# gyro_acc.net
KiCad netlist of a schematic drawn in EAGLE
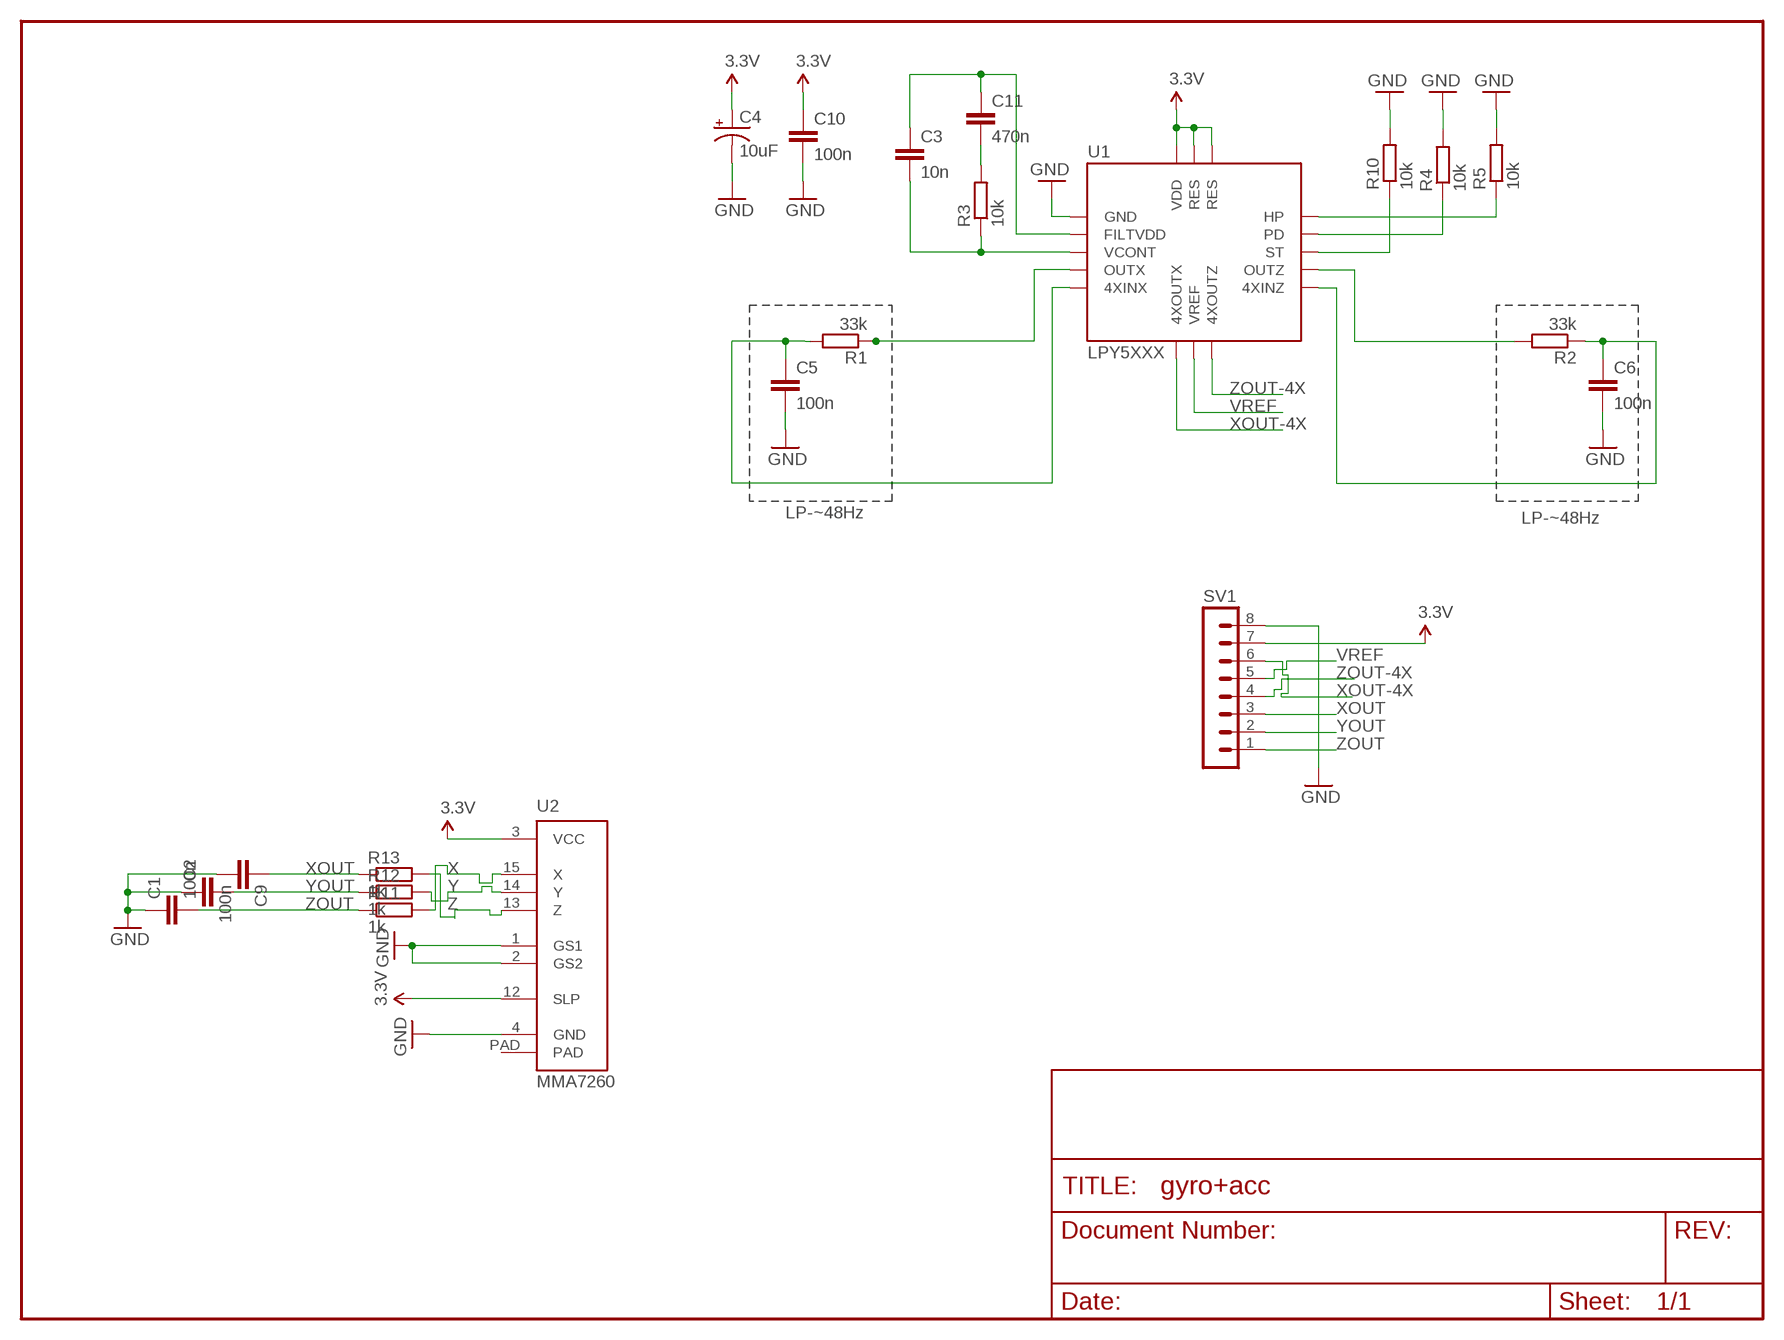
[diagram p0: schematic, sheet 1]

(export (version "E")
  (design (tool "Eeschema 10.0.6"))
  (components
    (comp (ref "C1")
      (value "100n")
      (footprint "eagle-import:C1206")
      (libsource (lib "eagle-import") (part "C-EUC1206"))
    )
    (comp (ref "C2")
      (value "C-EUC1206")
      (footprint "eagle-import:C1206")
      (libsource (lib "eagle-import") (part "C-EUC1206"))
    )
    (comp (ref "C3")
      (value "10n")
      (footprint "eagle-import:C1206")
      (libsource (lib "eagle-import") (part "C-EUC1206"))
    )
    (comp (ref "C4")
      (value "10uF")
      (footprint "eagle-import:EIA3216")
      (libsource (lib "eagle-import") (part "CAP_POL1206"))
    )
    (comp (ref "C5")
      (value "100n")
      (footprint "eagle-import:C1206")
      (libsource (lib "eagle-import") (part "C-EUC1206"))
    )
    (comp (ref "C6")
      (value "100n")
      (footprint "eagle-import:C1206")
      (libsource (lib "eagle-import") (part "C-EUC1206"))
    )
    (comp (ref "C9")
      (value "100n")
      (footprint "eagle-import:C1206")
      (libsource (lib "eagle-import") (part "C-EUC1206"))
    )
    (comp (ref "C10")
      (value "100n")
      (footprint "eagle-import:C1206")
      (libsource (lib "eagle-import") (part "C-EUC1206"))
    )
    (comp (ref "C11")
      (value "470n")
      (footprint "eagle-import:C1206")
      (libsource (lib "eagle-import") (part "C-EUC1206"))
    )
    (comp (ref "R1")
      (value "33k")
      (footprint "eagle-import:M1206")
      (libsource (lib "eagle-import") (part "R-EU_M1206"))
    )
    (comp (ref "R2")
      (value "33k")
      (footprint "eagle-import:M1206")
      (libsource (lib "eagle-import") (part "R-EU_M1206"))
    )
    (comp (ref "R3")
      (value "10k")
      (footprint "eagle-import:M1206")
      (libsource (lib "eagle-import") (part "R-EU_M1206"))
    )
    (comp (ref "R4")
      (value "10k")
      (footprint "eagle-import:M1206")
      (libsource (lib "eagle-import") (part "R-EU_M1206"))
    )
    (comp (ref "R5")
      (value "10k")
      (footprint "eagle-import:M1206")
      (libsource (lib "eagle-import") (part "R-EU_M1206"))
    )
    (comp (ref "R10")
      (value "10k")
      (footprint "eagle-import:M1206")
      (libsource (lib "eagle-import") (part "R-EU_M1206"))
    )
    (comp (ref "R11")
      (value "1k")
      (footprint "eagle-import:M1206")
      (libsource (lib "eagle-import") (part "R-EU_M1206"))
    )
    (comp (ref "R12")
      (value "1k")
      (footprint "eagle-import:M1206")
      (libsource (lib "eagle-import") (part "R-EU_M1206"))
    )
    (comp (ref "R13")
      (value "1k")
      (footprint "eagle-import:M1206")
      (libsource (lib "eagle-import") (part "R-EU_M1206"))
    )
    (comp (ref "SV1")
      (value "MA08-1")
      (footprint "eagle-import:MA08-1")
      (libsource (lib "eagle-import") (part "MA08-1"))
    )
    (comp (ref "U1")
      (value "LPY5XXX")
      (footprint "eagle-import:ST-GYRO")
      (libsource (lib "eagle-import") (part "ST-GYRO-PYSMD"))
    )
    (comp (ref "U2")
      (value "MMA7260")
      (footprint "eagle-import:MMA7260")
      (libsource (lib "eagle-import") (part "MMA7260"))
    )
  )
  (nets
    (net (code "1") (name "/VREF") (class "Default")
      (node (ref "SV1") (pin "5") (pinfunction "5_5") (pintype "passive"))
      (node (ref "U1") (pin "7") (pinfunction "VREF_7") (pintype "bidirectional"))
    )
    (net (code "2") (name "/X") (class "Default")
      (node (ref "R11") (pin "2") (pinfunction "2_2") (pintype "passive"))
      (node (ref "U2") (pin "15") (pinfunction "X_15") (pintype "bidirectional"))
    )
    (net (code "3") (name "/XOUT") (class "Default")
      (node (ref "C9") (pin "1") (pinfunction "1_1") (pintype "passive"))
      (node (ref "R13") (pin "1") (pinfunction "1_1") (pintype "passive"))
      (node (ref "SV1") (pin "3") (pinfunction "3_3") (pintype "passive"))
    )
    (net (code "4") (name "/XOUT-4X") (class "Default")
      (node (ref "SV1") (pin "6") (pinfunction "6_6") (pintype "passive"))
      (node (ref "U1") (pin "6") (pinfunction "4XOUTX_6") (pintype "bidirectional"))
    )
    (net (code "5") (name "/Y") (class "Default")
      (node (ref "R12") (pin "2") (pinfunction "2_2") (pintype "passive"))
      (node (ref "U2") (pin "14") (pinfunction "Y_14") (pintype "bidirectional"))
    )
    (net (code "6") (name "/YOUT") (class "Default")
      (node (ref "C2") (pin "2") (pinfunction "2_2") (pintype "passive"))
      (node (ref "R12") (pin "1") (pinfunction "1_1") (pintype "passive"))
      (node (ref "SV1") (pin "2") (pinfunction "2_2") (pintype "passive"))
    )
    (net (code "7") (name "/Z") (class "Default")
      (node (ref "R13") (pin "2") (pinfunction "2_2") (pintype "passive"))
      (node (ref "U2") (pin "13") (pinfunction "Z_13") (pintype "bidirectional"))
    )
    (net (code "8") (name "/ZOUT") (class "Default")
      (node (ref "C1") (pin "2") (pinfunction "2_2") (pintype "passive"))
      (node (ref "R11") (pin "1") (pinfunction "1_1") (pintype "passive"))
      (node (ref "SV1") (pin "1") (pinfunction "1_1") (pintype "passive"))
    )
    (net (code "9") (name "/ZOUT-4X") (class "Default")
      (node (ref "SV1") (pin "4") (pinfunction "4_4") (pintype "passive"))
      (node (ref "U1") (pin "8") (pinfunction "4XOUTZ_8") (pintype "bidirectional"))
    )
    (net (code "10") (name "3.3V") (class "Default")
      (node (ref "C10") (pin "1") (pinfunction "1_1") (pintype "passive"))
      (node (ref "C4") (pin "A") (pinfunction "+_A") (pintype "passive"))
      (node (ref "SV1") (pin "7") (pinfunction "7_7") (pintype "passive"))
      (node (ref "U1") (pin "14") (pinfunction "RES_14") (pintype "bidirectional"))
      (node (ref "U1") (pin "15") (pinfunction "RES_15") (pintype "bidirectional"))
      (node (ref "U1") (pin "16") (pinfunction "VDD_16") (pintype "bidirectional"))
      (node (ref "U2") (pin "12") (pinfunction "SLP_12") (pintype "bidirectional"))
      (node (ref "U2") (pin "3") (pinfunction "VCC_3") (pintype "bidirectional"))
    )
    (net (code "11") (name "GND") (class "Default")
      (node (ref "C1") (pin "1") (pinfunction "1_1") (pintype "passive"))
      (node (ref "C10") (pin "2") (pinfunction "2_2") (pintype "passive"))
      (node (ref "C2") (pin "1") (pinfunction "1_1") (pintype "passive"))
      (node (ref "C4") (pin "C") (pinfunction "-_C") (pintype "passive"))
      (node (ref "C5") (pin "2") (pinfunction "2_2") (pintype "passive"))
      (node (ref "C6") (pin "2") (pinfunction "2_2") (pintype "passive"))
      (node (ref "C9") (pin "2") (pinfunction "2_2") (pintype "passive"))
      (node (ref "R10") (pin "2") (pinfunction "2_2") (pintype "passive"))
      (node (ref "R4") (pin "2") (pinfunction "2_2") (pintype "passive"))
      (node (ref "R5") (pin "2") (pinfunction "2_2") (pintype "passive"))
      (node (ref "SV1") (pin "8") (pinfunction "8_8") (pintype "passive"))
      (node (ref "U1") (pin "1") (pinfunction "GND_1") (pintype "bidirectional"))
      (node (ref "U2") (pin "1") (pinfunction "GS1_1") (pintype "bidirectional"))
      (node (ref "U2") (pin "2") (pinfunction "GS2_2") (pintype "bidirectional"))
      (node (ref "U2") (pin "4") (pinfunction "GND_4") (pintype "bidirectional"))
    )
    (net (code "12") (name "Net-(C11-Pad2)") (class "Default")
      (node (ref "C11") (pin "2") (pinfunction "2_2") (pintype "passive"))
      (node (ref "R3") (pin "2") (pinfunction "2_2") (pintype "passive"))
    )
    (net (code "13") (name "Net-(U1-4XINX)") (class "Default")
      (node (ref "C5") (pin "1") (pinfunction "1_1") (pintype "passive"))
      (node (ref "R1") (pin "2") (pinfunction "2_2") (pintype "passive"))
      (node (ref "U1") (pin "5") (pinfunction "4XINX_5") (pintype "bidirectional"))
    )
    (net (code "14") (name "Net-(U1-4XINZ)") (class "Default")
      (node (ref "C6") (pin "1") (pinfunction "1_1") (pintype "passive"))
      (node (ref "R2") (pin "1") (pinfunction "1_1") (pintype "passive"))
      (node (ref "U1") (pin "9") (pinfunction "4XINZ_9") (pintype "bidirectional"))
    )
    (net (code "15") (name "Net-(U1-FILTVDD)") (class "Default")
      (node (ref "C11") (pin "1") (pinfunction "1_1") (pintype "passive"))
      (node (ref "C3") (pin "1") (pinfunction "1_1") (pintype "passive"))
      (node (ref "U1") (pin "2") (pinfunction "FILTVDD_2") (pintype "bidirectional"))
    )
    (net (code "16") (name "Net-(U1-HP)") (class "Default")
      (node (ref "R5") (pin "1") (pinfunction "1_1") (pintype "passive"))
      (node (ref "U1") (pin "13") (pinfunction "HP_13") (pintype "bidirectional"))
    )
    (net (code "17") (name "Net-(U1-OUTX)") (class "Default")
      (node (ref "R1") (pin "1") (pinfunction "1_1") (pintype "passive"))
      (node (ref "U1") (pin "4") (pinfunction "OUTX_4") (pintype "bidirectional"))
    )
    (net (code "18") (name "Net-(U1-OUTZ)") (class "Default")
      (node (ref "R2") (pin "2") (pinfunction "2_2") (pintype "passive"))
      (node (ref "U1") (pin "10") (pinfunction "OUTZ_10") (pintype "bidirectional"))
    )
    (net (code "19") (name "Net-(U1-PD)") (class "Default")
      (node (ref "R4") (pin "1") (pinfunction "1_1") (pintype "passive"))
      (node (ref "U1") (pin "12") (pinfunction "PD_12") (pintype "bidirectional"))
    )
    (net (code "20") (name "Net-(U1-ST)") (class "Default")
      (node (ref "R10") (pin "1") (pinfunction "1_1") (pintype "passive"))
      (node (ref "U1") (pin "11") (pinfunction "ST_11") (pintype "bidirectional"))
    )
    (net (code "21") (name "Net-(U1-VCONT)") (class "Default")
      (node (ref "C3") (pin "2") (pinfunction "2_2") (pintype "passive"))
      (node (ref "R3") (pin "1") (pinfunction "1_1") (pintype "passive"))
      (node (ref "U1") (pin "3") (pinfunction "VCONT_3") (pintype "bidirectional"))
    )
    (net (code "22") (name "unconnected-(U2-PadPAD)") (class "Default")
      (node (ref "U2") (pin "PAD") (pinfunction "PAD_PAD") (pintype "bidirectional"))
    )
  )
)
